# WSS-Board.net
KiCad netlist of a schematic drawn in EAGLE
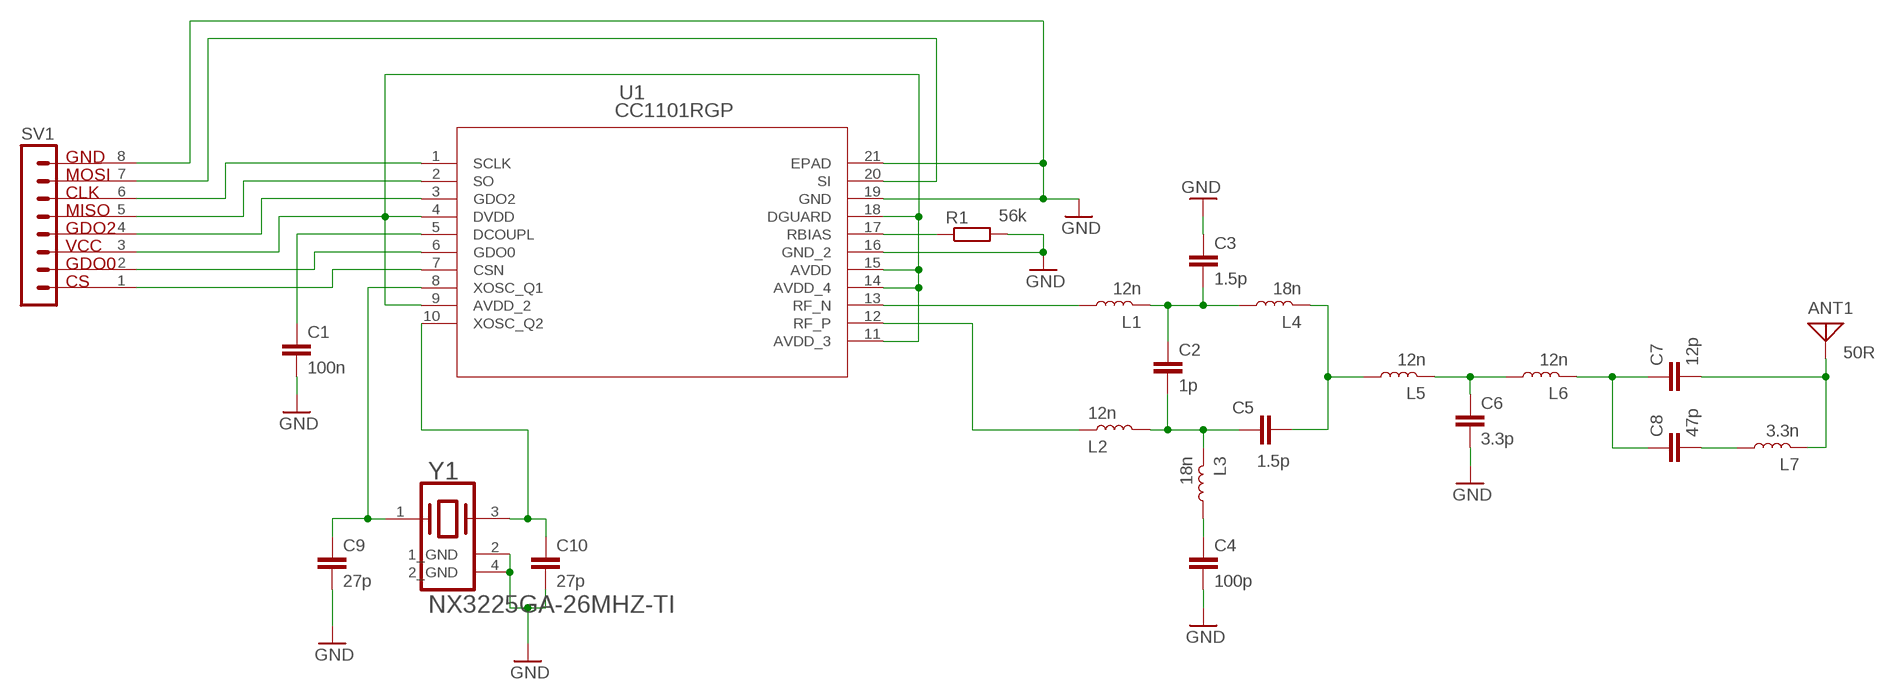
[diagram p0: schematic, sheet 1]

(export (version "E")
  (design (tool "Eeschema 10.0.6"))
  (components
    (comp (ref "ANT1")
      (value "50R")
      (footprint "eagle-import:PAD-01")
      (libsource (lib "eagle-import") (part "ANTENNA"))
    )
    (comp (ref "C1")
      (value "100n")
      (footprint "eagle-import:C0603")
      (libsource (lib "eagle-import") (part "C-EUC0603"))
    )
    (comp (ref "C2")
      (value "1p")
      (footprint "eagle-import:C0603")
      (libsource (lib "eagle-import") (part "C-EUC0603"))
    )
    (comp (ref "C3")
      (value "1.5p")
      (footprint "eagle-import:C0603")
      (libsource (lib "eagle-import") (part "C-EUC0603"))
    )
    (comp (ref "C4")
      (value "100p")
      (footprint "eagle-import:C0603")
      (libsource (lib "eagle-import") (part "C-EUC0603"))
    )
    (comp (ref "C5")
      (value "1.5p")
      (footprint "eagle-import:C0603")
      (libsource (lib "eagle-import") (part "C-EUC0603"))
    )
    (comp (ref "C6")
      (value "3.3p")
      (footprint "eagle-import:C0603")
      (libsource (lib "eagle-import") (part "C-EUC0603"))
    )
    (comp (ref "C7")
      (value "12p")
      (footprint "eagle-import:C0603")
      (libsource (lib "eagle-import") (part "C-EUC0603"))
    )
    (comp (ref "C8")
      (value "47p")
      (footprint "eagle-import:C0603")
      (libsource (lib "eagle-import") (part "C-EUC0603"))
    )
    (comp (ref "C9")
      (value "27p")
      (footprint "eagle-import:C0603")
      (libsource (lib "eagle-import") (part "C-EUC0603"))
    )
    (comp (ref "C10")
      (value "27p")
      (footprint "eagle-import:C0603")
      (libsource (lib "eagle-import") (part "C-EUC0603"))
    )
    (comp (ref "L1")
      (value "12n")
      (footprint "eagle-import:0603")
      (libsource (lib "eagle-import") (part "INDUCTOR-0603-33NH"))
    )
    (comp (ref "L2")
      (value "12n")
      (footprint "eagle-import:0603")
      (libsource (lib "eagle-import") (part "INDUCTOR-0603-33NH"))
    )
    (comp (ref "L3")
      (value "18n")
      (footprint "eagle-import:0603")
      (libsource (lib "eagle-import") (part "INDUCTOR-0603-33NH"))
    )
    (comp (ref "L4")
      (value "18n")
      (footprint "eagle-import:0603")
      (libsource (lib "eagle-import") (part "INDUCTOR-0603-33NH"))
    )
    (comp (ref "L5")
      (value "12n")
      (footprint "eagle-import:0603")
      (libsource (lib "eagle-import") (part "INDUCTOR-0603-33NH"))
    )
    (comp (ref "L6")
      (value "12n")
      (footprint "eagle-import:0603")
      (libsource (lib "eagle-import") (part "INDUCTOR-0603-33NH"))
    )
    (comp (ref "L7")
      (value "3.3n")
      (footprint "eagle-import:0603")
      (libsource (lib "eagle-import") (part "INDUCTOR-0603-33NH"))
    )
    (comp (ref "R1")
      (value "56k")
      (footprint "eagle-import:R0603")
      (libsource (lib "eagle-import") (part "R-EU_R0603"))
    )
    (comp (ref "SV1")
      (value "MA08-1")
      (footprint "eagle-import:MA08-1")
      (libsource (lib "eagle-import") (part "MA08-1"))
    )
    (comp (ref "U1")
      (value "CC1101RGP")
      (footprint "eagle-import:RGP20_2P4X2P4")
      (fields (field (name "COPYRIGHT") "Copyright (C) 2022 Ultra Librarian. All rights reserved."))
      (libsource (lib "eagle-import") (part "CC1101RGP"))
    )
    (comp (ref "Y1")
      (value "NDK_NX3225GA-26MHZ-TINDK_NX3225GA-26MHZ-TI_0_0")
      (footprint "eagle-import:NDK_NX3225GA-26MHZ-TI_0")
      (fields
        (field (name "DIGIKEY_PART_NUMBER") "644-1160-1-ND")
        (field (name "MF") "NDK")
        (field (name "MPN") "NX3225GA-26MHZ-TI")
      )
      (libsource (lib "eagle-import") (part "NDK_NX3225GA-26MHZ-TINDK_NX3225GA-26MHZ-TI_0_0"))
    )
  )
  (nets
    (net (code "1") (name "GND") (class "Default")
      (node (ref "C1") (pin "2") (pinfunction "2_2") (pintype "passive"))
      (node (ref "C10") (pin "2") (pinfunction "2_2") (pintype "passive"))
      (node (ref "C3") (pin "1") (pinfunction "1_1") (pintype "passive"))
      (node (ref "C4") (pin "2") (pinfunction "2_2") (pintype "passive"))
      (node (ref "C6") (pin "2") (pinfunction "2_2") (pintype "passive"))
      (node (ref "C9") (pin "2") (pinfunction "2_2") (pintype "passive"))
      (node (ref "R1") (pin "2") (pinfunction "2_2") (pintype "passive"))
      (node (ref "SV1") (pin "8") (pinfunction "8_8") (pintype "passive"))
      (node (ref "U1") (pin "16") (pinfunction "GND_2_16") (pintype "power_in"))
      (node (ref "U1") (pin "19") (pinfunction "GND_19") (pintype "power_in"))
      (node (ref "U1") (pin "21") (pinfunction "EPAD_21") (pintype "power_in"))
      (node (ref "Y1") (pin "2") (pinfunction "1_GND_2") (pintype "bidirectional"))
      (node (ref "Y1") (pin "4") (pinfunction "2_GND_4") (pintype "bidirectional"))
    )
    (net (code "2") (name "Net-(ANT1-Pad1)") (class "Default")
      (node (ref "ANT1") (pin "1") (pinfunction "1_1") (pintype "output"))
      (node (ref "C7") (pin "2") (pinfunction "2_2") (pintype "passive"))
      (node (ref "L7") (pin "2") (pinfunction "2_2") (pintype "passive"))
    )
    (net (code "3") (name "Net-(C2-Pad1)") (class "Default")
      (node (ref "C2") (pin "1") (pinfunction "1_1") (pintype "passive"))
      (node (ref "C3") (pin "2") (pinfunction "2_2") (pintype "passive"))
      (node (ref "L1") (pin "2") (pinfunction "2_2") (pintype "passive"))
      (node (ref "L4") (pin "1") (pinfunction "1_1") (pintype "passive"))
    )
    (net (code "4") (name "Net-(C2-Pad2)") (class "Default")
      (node (ref "C2") (pin "2") (pinfunction "2_2") (pintype "passive"))
      (node (ref "C5") (pin "1") (pinfunction "1_1") (pintype "passive"))
      (node (ref "L2") (pin "1") (pinfunction "1_1") (pintype "passive"))
      (node (ref "L3") (pin "2") (pinfunction "2_2") (pintype "passive"))
    )
    (net (code "5") (name "Net-(C4-Pad1)") (class "Default")
      (node (ref "C4") (pin "1") (pinfunction "1_1") (pintype "passive"))
      (node (ref "L3") (pin "1") (pinfunction "1_1") (pintype "passive"))
    )
    (net (code "6") (name "Net-(C5-Pad2)") (class "Default")
      (node (ref "C5") (pin "2") (pinfunction "2_2") (pintype "passive"))
      (node (ref "L4") (pin "2") (pinfunction "2_2") (pintype "passive"))
      (node (ref "L5") (pin "1") (pinfunction "1_1") (pintype "passive"))
    )
    (net (code "7") (name "Net-(C6-Pad1)") (class "Default")
      (node (ref "C6") (pin "1") (pinfunction "1_1") (pintype "passive"))
      (node (ref "L5") (pin "2") (pinfunction "2_2") (pintype "passive"))
      (node (ref "L6") (pin "1") (pinfunction "1_1") (pintype "passive"))
    )
    (net (code "8") (name "Net-(C7-Pad1)") (class "Default")
      (node (ref "C7") (pin "1") (pinfunction "1_1") (pintype "passive"))
      (node (ref "C8") (pin "1") (pinfunction "1_1") (pintype "passive"))
      (node (ref "L6") (pin "2") (pinfunction "2_2") (pintype "passive"))
    )
    (net (code "9") (name "Net-(C8-Pad2)") (class "Default")
      (node (ref "C8") (pin "2") (pinfunction "2_2") (pintype "passive"))
      (node (ref "L7") (pin "1") (pinfunction "1_1") (pintype "passive"))
    )
    (net (code "10") (name "Net-(U1-AVDD)") (class "Default")
      (node (ref "SV1") (pin "3") (pinfunction "3_3") (pintype "passive"))
      (node (ref "U1") (pin "11") (pinfunction "AVDD_3_11") (pintype "power_in"))
      (node (ref "U1") (pin "14") (pinfunction "AVDD_4_14") (pintype "power_in"))
      (node (ref "U1") (pin "15") (pinfunction "AVDD_15") (pintype "power_in"))
      (node (ref "U1") (pin "18") (pinfunction "DGUARD_18") (pintype "power_in"))
      (node (ref "U1") (pin "4") (pinfunction "DVDD_4") (pintype "power_in"))
      (node (ref "U1") (pin "9") (pinfunction "AVDD_2_9") (pintype "power_in"))
    )
    (net (code "11") (name "Net-(U1-CSN)") (class "Default")
      (node (ref "SV1") (pin "1") (pinfunction "1_1") (pintype "passive"))
      (node (ref "U1") (pin "7") (pinfunction "CSN_7") (pintype "input"))
    )
    (net (code "12") (name "Net-(U1-DCOUPL)") (class "Default")
      (node (ref "C1") (pin "1") (pinfunction "1_1") (pintype "passive"))
      (node (ref "U1") (pin "5") (pinfunction "DCOUPL_5") (pintype "power_in"))
    )
    (net (code "13") (name "Net-(U1-GDO0)") (class "Default")
      (node (ref "SV1") (pin "2") (pinfunction "2_2") (pintype "passive"))
      (node (ref "U1") (pin "6") (pinfunction "GDO0_6") (pintype "bidirectional"))
    )
    (net (code "14") (name "Net-(U1-GDO2)") (class "Default")
      (node (ref "SV1") (pin "4") (pinfunction "4_4") (pintype "passive"))
      (node (ref "U1") (pin "3") (pinfunction "GDO2_3") (pintype "output"))
    )
    (net (code "15") (name "Net-(U1-RBIAS)") (class "Default")
      (node (ref "R1") (pin "1") (pinfunction "1_1") (pintype "passive"))
      (node (ref "U1") (pin "17") (pinfunction "RBIAS_17") (pintype "bidirectional"))
    )
    (net (code "16") (name "Net-(U1-RF_N)") (class "Default")
      (node (ref "L1") (pin "1") (pinfunction "1_1") (pintype "passive"))
      (node (ref "U1") (pin "13") (pinfunction "RF_N_13") (pintype "bidirectional"))
    )
    (net (code "17") (name "Net-(U1-RF_P)") (class "Default")
      (node (ref "L2") (pin "2") (pinfunction "2_2") (pintype "passive"))
      (node (ref "U1") (pin "12") (pinfunction "RF_P_12") (pintype "bidirectional"))
    )
    (net (code "18") (name "Net-(U1-SCLK)") (class "Default")
      (node (ref "SV1") (pin "6") (pinfunction "6_6") (pintype "passive"))
      (node (ref "U1") (pin "1") (pinfunction "SCLK_1") (pintype "passive"))
    )
    (net (code "19") (name "Net-(U1-SI)") (class "Default")
      (node (ref "SV1") (pin "7") (pinfunction "7_7") (pintype "passive"))
      (node (ref "U1") (pin "20") (pinfunction "SI_20") (pintype "input"))
    )
    (net (code "20") (name "Net-(U1-SO)") (class "Default")
      (node (ref "SV1") (pin "5") (pinfunction "5_5") (pintype "passive"))
      (node (ref "U1") (pin "2") (pinfunction "SO_2") (pintype "output"))
    )
    (net (code "21") (name "Net-(U1-XOSC_Q1)") (class "Default")
      (node (ref "C9") (pin "1") (pinfunction "1_1") (pintype "passive"))
      (node (ref "U1") (pin "8") (pinfunction "XOSC_Q1_8") (pintype "bidirectional"))
      (node (ref "Y1") (pin "1") (pinfunction "1_1") (pintype "bidirectional"))
    )
    (net (code "22") (name "Net-(U1-XOSC_Q2)") (class "Default")
      (node (ref "C10") (pin "1") (pinfunction "1_1") (pintype "passive"))
      (node (ref "U1") (pin "10") (pinfunction "XOSC_Q2_10") (pintype "bidirectional"))
      (node (ref "Y1") (pin "3") (pinfunction "3_3") (pintype "bidirectional"))
    )
  )
)
